# vga_audio.net
KiCad netlist of a schematic drawn in Altium Designer
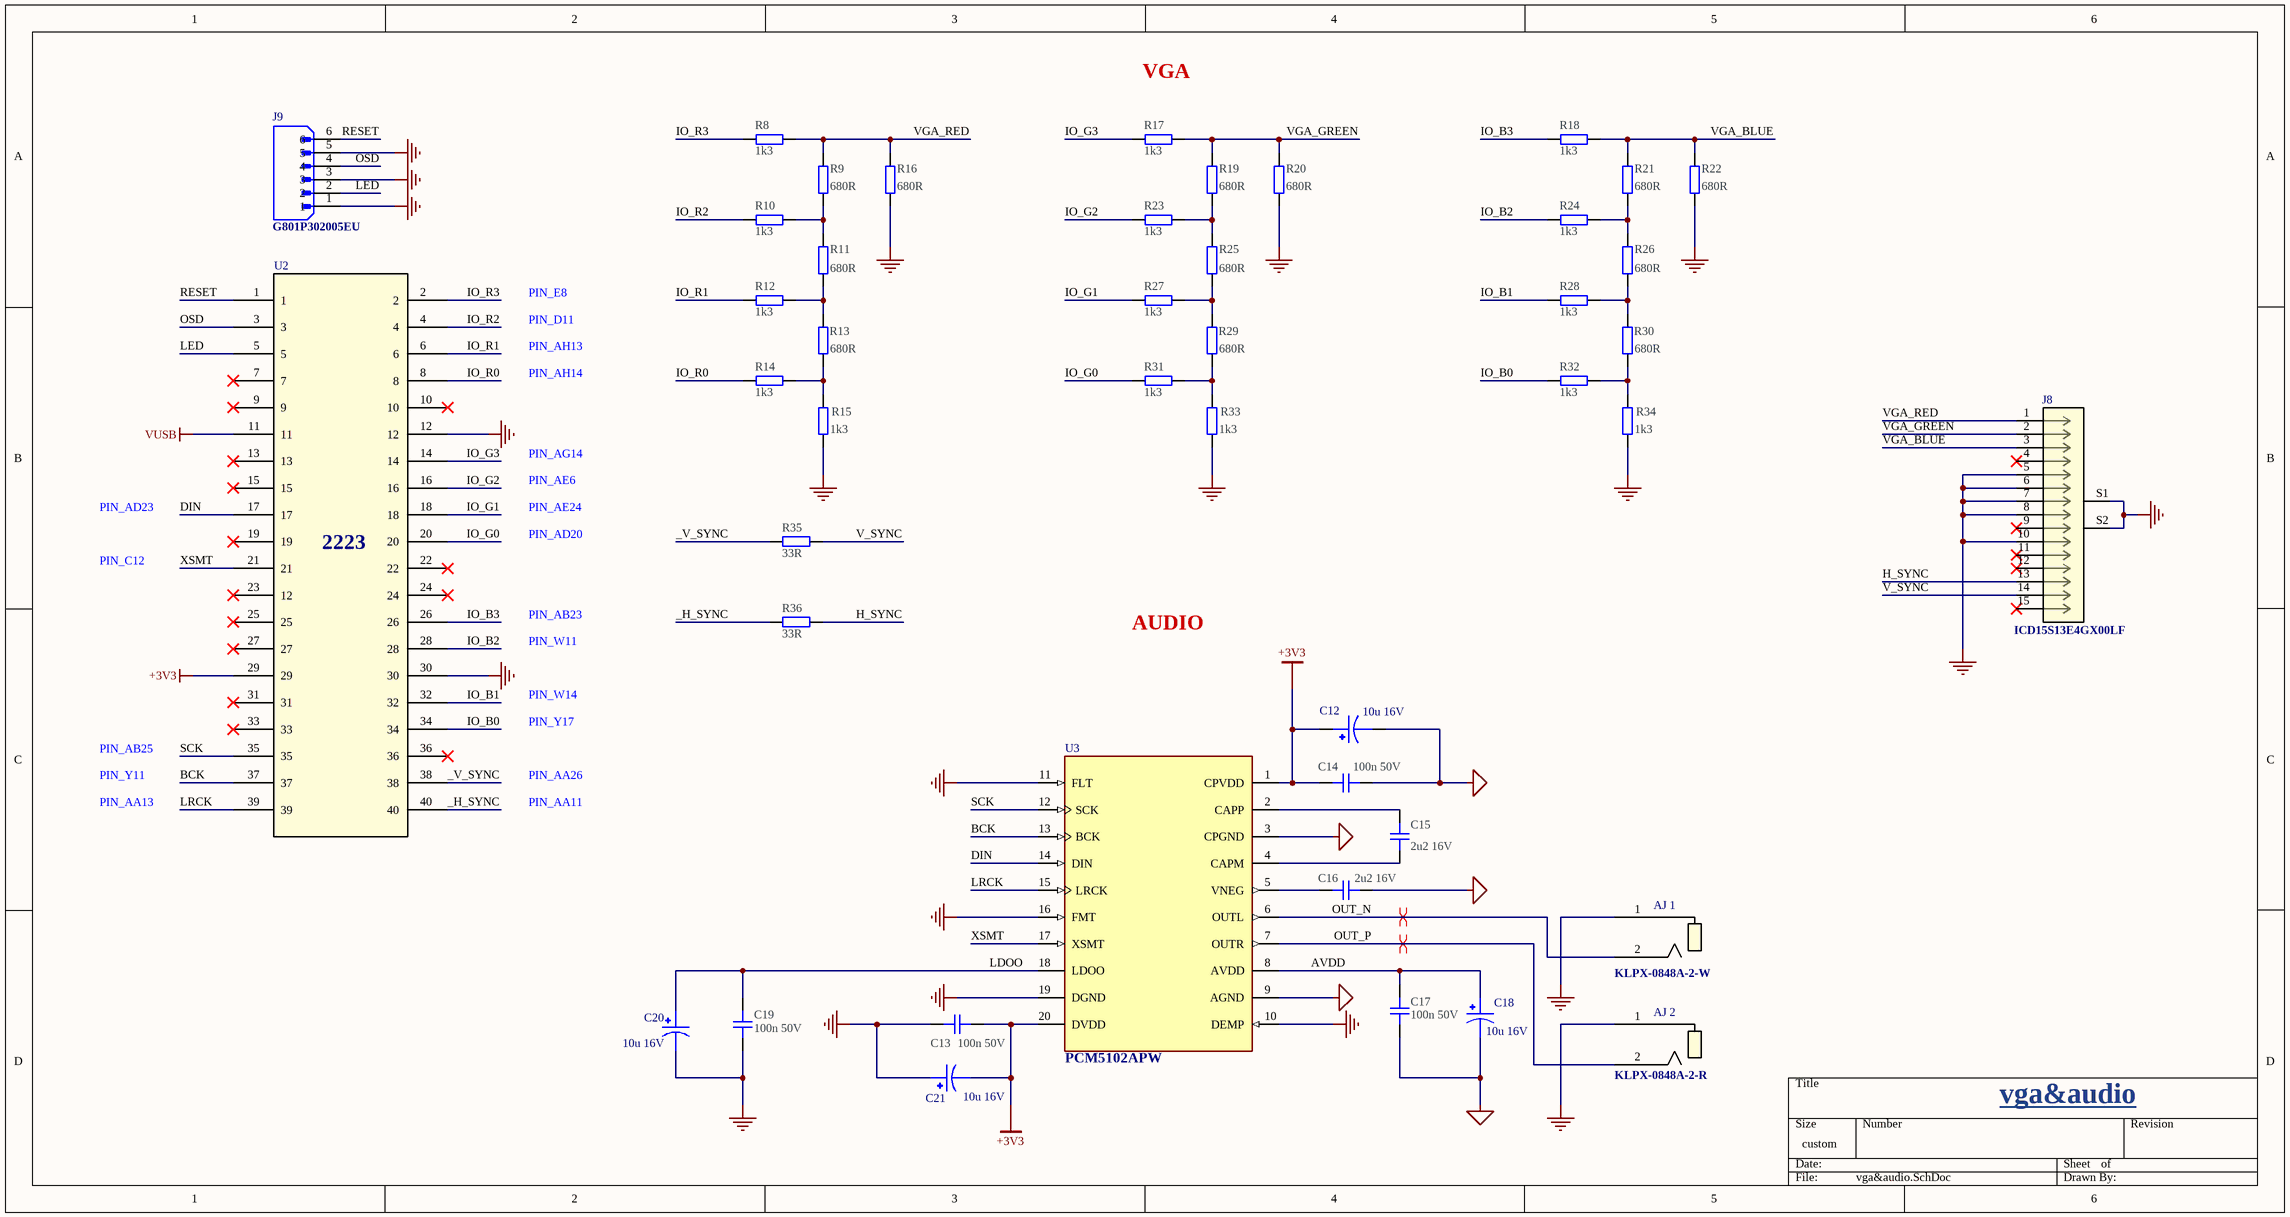
[diagram p0: vga&audio.SchDoc]

(export (version "E")
  (design (tool "Eeschema 10.0.6"))
  (components
    (comp (ref "AJ 1")
      (value "KLPX-0848A-2-W")
      (footprint "KLPX0848A2W")
      (description "Description")
      (fields
        (field (name "MANUFACTURER_PART_NUMBER") "KLPX-0848A-2-R")
        (field (name "COPYRIGHT") "Copyright (C) 2025 Ultra Librarian. All rights reserved.")
      )
      (libsource (lib "Sch_Lib") (part "KLPX-0848A-2-W"))
    )
    (comp (ref "AJ 2")
      (value "KLPX-0848A-2-R")
      (footprint "KLPX0848A2R")
      (description "Description")
      (fields (field (name "COPYRIGHT") "Copyright (C) 2025 Ultra Librarian. All rights reserved."))
      (libsource (lib "Sch_Lib") (part "KLPX-0848A-2-R"))
    )
    (comp (ref "C12")
      (value "10u 16V")
      (footprint "CAPMP3216X180N")
      (description "10 ÂµF Molded Tantalum Capacitors 16 V 1206 (3216 Metric) 3Ohm")
      (fields (field (name "MF") "KYOCERA AVX") (field (name "MP") "TAJA106K016RNJ"))
      (libsource (lib "") (part "TAJA106K016RNJ_1"))
    )
    (comp (ref "C13")
      (value "100n 50V")
      (footprint "CAPC1005X04L")
      (description "Capacitor, X5R, ±20%")
      (fields
        (field (name "PART NUMBER") "C0402-4µ7")
        (field (name "MANUFACTURER") "N.A.")
        (field (name "AUTHOR") "rsk")
      )
      (libsource (lib "Sch_Lib") (part "C0402-4µ7"))
    )
    (comp (ref "C14")
      (value "100n 50V")
      (footprint "CAPC1005X04L")
      (description "Capacitor, X5R, ±20%")
      (fields
        (field (name "PART NUMBER") "C0402-4µ7")
        (field (name "MANUFACTURER") "N.A.")
        (field (name "AUTHOR") "rsk")
      )
      (libsource (lib "Sch_Lib") (part "C0402-4µ7"))
    )
    (comp (ref "C15")
      (value "2u2 16V")
      (footprint "CAPC1005X04L")
      (description "Capacitor, X5R, ±20%")
      (fields
        (field (name "PART NUMBER") "C0402-4µ7")
        (field (name "MANUFACTURER") "N.A.")
        (field (name "AUTHOR") "rsk")
      )
      (libsource (lib "Sch_Lib") (part "C0402-4µ7"))
    )
    (comp (ref "C16")
      (value "2u2 16V")
      (footprint "CAPC1005X04L")
      (description "Capacitor, X5R, ±20%")
      (fields
        (field (name "PART NUMBER") "C0402-4µ7")
        (field (name "MANUFACTURER") "N.A.")
        (field (name "AUTHOR") "rsk")
      )
      (libsource (lib "Sch_Lib") (part "C0402-4µ7"))
    )
    (comp (ref "C17")
      (value "100n 50V")
      (footprint "CAPC1005X04L")
      (description "Capacitor, X5R, ±20%")
      (fields
        (field (name "PART NUMBER") "C0402-4µ7")
        (field (name "MANUFACTURER") "N.A.")
        (field (name "AUTHOR") "rsk")
      )
      (libsource (lib "Sch_Lib") (part "C0402-4µ7"))
    )
    (comp (ref "C18")
      (value "10u 16V")
      (footprint "CAPMP3216X180N")
      (description "10 ÂµF Molded Tantalum Capacitors 16 V 1206 (3216 Metric) 3Ohm")
      (fields (field (name "MF") "KYOCERA AVX") (field (name "MP") "TAJA106K016RNJ"))
      (libsource (lib "") (part "TAJA106K016RNJ_2"))
    )
    (comp (ref "C19")
      (value "100n 50V")
      (footprint "CAPC1005X04L")
      (description "Capacitor, X5R, ±20%")
      (fields
        (field (name "PART NUMBER") "C0402-4µ7")
        (field (name "MANUFACTURER") "N.A.")
        (field (name "AUTHOR") "rsk")
      )
      (libsource (lib "Sch_Lib") (part "C0402-4µ7"))
    )
    (comp (ref "C20")
      (value "10u 16V")
      (footprint "CAPMP3216X180N")
      (description "10 ÂµF Molded Tantalum Capacitors 16 V 1206 (3216 Metric) 3Ohm")
      (fields (field (name "MF") "KYOCERA AVX") (field (name "MP") "TAJA106K016RNJ"))
      (libsource (lib "") (part "TAJA106K016RNJ_2"))
    )
    (comp (ref "C21")
      (value "10u 16V")
      (footprint "CAPMP3216X180N")
      (description "10 ÂµF Molded Tantalum Capacitors 16 V 1206 (3216 Metric) 3Ohm")
      (fields (field (name "MF") "KYOCERA AVX") (field (name "MP") "TAJA106K016RNJ"))
      (libsource (lib "Sch_Lib") (part "TAJA106K016RNJ"))
    )
    (comp (ref "J8")
      (value "ICD15S13E4GX00LF")
      (footprint "AMPHENOL_ICD15S13E4GX00LF")
      (description "Conn High Density D-Sub SKT 15 POS 2.28mm Solder RA Thru-Hole 15 Terminal 1 Port")
      (fields (field (name "MF") "Amphenol"))
      (libsource (lib "Sch_Lib") (part "ICD15S13E4GX00LF"))
    )
    (comp (ref "J9")
      (value "G801P302005EU")
      (footprint "AMPHENOL_G801P302005EU")
      (fields (field (name "MF") "{'manufacturer': u'Amphenol ICC (Commercial Products)'}"))
      (libsource (lib "Sch_Lib") (part "G801P302005EU"))
    )
    (comp (ref "R8")
      (value "1k3")
      (footprint "RESC1005X04L")
      (description "Resistor, ±5%, 0.063W")
      (fields
        (field (name "PART NUMBER") "R0402-0R")
        (field (name "MANUFACTURER") "N.A.")
        (field (name "AUTHOR") "rsk")
      )
      (libsource (lib "Sch_Lib") (part "R0402-0R"))
    )
    (comp (ref "R9")
      (value "680R")
      (footprint "RESC1005X04L")
      (description "Resistor, ±5%, 0.063W")
      (fields
        (field (name "PART NUMBER") "R0402-0R")
        (field (name "MANUFACTURER") "N.A.")
        (field (name "AUTHOR") "rsk")
      )
      (libsource (lib "Sch_Lib") (part "R0402-0R"))
    )
    (comp (ref "R10")
      (value "1k3")
      (footprint "RESC1005X04L")
      (description "Resistor, ±5%, 0.063W")
      (fields
        (field (name "PART NUMBER") "R0402-0R")
        (field (name "MANUFACTURER") "N.A.")
        (field (name "AUTHOR") "rsk")
      )
      (libsource (lib "Sch_Lib") (part "R0402-0R"))
    )
    (comp (ref "R11")
      (value "680R")
      (footprint "RESC1005X04L")
      (description "Resistor, ±5%, 0.063W")
      (fields
        (field (name "PART NUMBER") "R0402-0R")
        (field (name "MANUFACTURER") "N.A.")
        (field (name "AUTHOR") "rsk")
      )
      (libsource (lib "Sch_Lib") (part "R0402-0R"))
    )
    (comp (ref "R12")
      (value "1k3")
      (footprint "RESC1005X04L")
      (description "Resistor, ±5%, 0.063W")
      (fields
        (field (name "PART NUMBER") "R0402-0R")
        (field (name "MANUFACTURER") "N.A.")
        (field (name "AUTHOR") "rsk")
      )
      (libsource (lib "Sch_Lib") (part "R0402-0R"))
    )
    (comp (ref "R13")
      (value "680R")
      (footprint "RESC1005X04L")
      (description "Resistor, ±5%, 0.063W")
      (fields
        (field (name "PART NUMBER") "R0402-0R")
        (field (name "MANUFACTURER") "N.A.")
        (field (name "AUTHOR") "rsk")
      )
      (libsource (lib "Sch_Lib") (part "R0402-0R"))
    )
    (comp (ref "R14")
      (value "1k3")
      (footprint "RESC1005X04L")
      (description "Resistor, ±5%, 0.063W")
      (fields
        (field (name "PART NUMBER") "R0402-0R")
        (field (name "MANUFACTURER") "N.A.")
        (field (name "AUTHOR") "rsk")
      )
      (libsource (lib "Sch_Lib") (part "R0402-0R"))
    )
    (comp (ref "R15")
      (value "1k3")
      (footprint "RESC1005X04L")
      (description "Resistor, ±5%, 0.063W")
      (fields
        (field (name "PART NUMBER") "R0402-0R")
        (field (name "MANUFACTURER") "N.A.")
        (field (name "AUTHOR") "rsk")
      )
      (libsource (lib "Sch_Lib") (part "R0402-0R"))
    )
    (comp (ref "R16")
      (value "680R")
      (footprint "RESC1005X04L")
      (description "Resistor, ±5%, 0.063W")
      (fields
        (field (name "PART NUMBER") "R0402-0R")
        (field (name "MANUFACTURER") "N.A.")
        (field (name "AUTHOR") "rsk")
      )
      (libsource (lib "Sch_Lib") (part "R0402-0R"))
    )
    (comp (ref "R17")
      (value "1k3")
      (footprint "RESC1005X04L")
      (description "Resistor, ±5%, 0.063W")
      (fields
        (field (name "PART NUMBER") "R0402-0R")
        (field (name "MANUFACTURER") "N.A.")
        (field (name "AUTHOR") "rsk")
      )
      (libsource (lib "Sch_Lib") (part "R0402-0R"))
    )
    (comp (ref "R18")
      (value "1k3")
      (footprint "RESC1005X04L")
      (description "Resistor, ±5%, 0.063W")
      (fields
        (field (name "PART NUMBER") "R0402-0R")
        (field (name "MANUFACTURER") "N.A.")
        (field (name "AUTHOR") "rsk")
      )
      (libsource (lib "Sch_Lib") (part "R0402-0R"))
    )
    (comp (ref "R19")
      (value "680R")
      (footprint "RESC1005X04L")
      (description "Resistor, ±5%, 0.063W")
      (fields
        (field (name "PART NUMBER") "R0402-0R")
        (field (name "MANUFACTURER") "N.A.")
        (field (name "AUTHOR") "rsk")
      )
      (libsource (lib "Sch_Lib") (part "R0402-0R"))
    )
    (comp (ref "R20")
      (value "680R")
      (footprint "RESC1005X04L")
      (description "Resistor, ±5%, 0.063W")
      (fields
        (field (name "PART NUMBER") "R0402-0R")
        (field (name "MANUFACTURER") "N.A.")
        (field (name "AUTHOR") "rsk")
      )
      (libsource (lib "Sch_Lib") (part "R0402-0R"))
    )
    (comp (ref "R21")
      (value "680R")
      (footprint "RESC1005X04L")
      (description "Resistor, ±5%, 0.063W")
      (fields
        (field (name "PART NUMBER") "R0402-0R")
        (field (name "MANUFACTURER") "N.A.")
        (field (name "AUTHOR") "rsk")
      )
      (libsource (lib "Sch_Lib") (part "R0402-0R"))
    )
    (comp (ref "R22")
      (value "680R")
      (footprint "RESC1005X04L")
      (description "Resistor, ±5%, 0.063W")
      (fields
        (field (name "PART NUMBER") "R0402-0R")
        (field (name "MANUFACTURER") "N.A.")
        (field (name "AUTHOR") "rsk")
      )
      (libsource (lib "Sch_Lib") (part "R0402-0R"))
    )
    (comp (ref "R23")
      (value "1k3")
      (footprint "RESC1005X04L")
      (description "Resistor, ±5%, 0.063W")
      (fields
        (field (name "PART NUMBER") "R0402-0R")
        (field (name "MANUFACTURER") "N.A.")
        (field (name "AUTHOR") "rsk")
      )
      (libsource (lib "Sch_Lib") (part "R0402-0R"))
    )
    (comp (ref "R24")
      (value "1k3")
      (footprint "RESC1005X04L")
      (description "Resistor, ±5%, 0.063W")
      (fields
        (field (name "PART NUMBER") "R0402-0R")
        (field (name "MANUFACTURER") "N.A.")
        (field (name "AUTHOR") "rsk")
      )
      (libsource (lib "Sch_Lib") (part "R0402-0R"))
    )
    (comp (ref "R25")
      (value "680R")
      (footprint "RESC1005X04L")
      (description "Resistor, ±5%, 0.063W")
      (fields
        (field (name "PART NUMBER") "R0402-0R")
        (field (name "MANUFACTURER") "N.A.")
        (field (name "AUTHOR") "rsk")
      )
      (libsource (lib "Sch_Lib") (part "R0402-0R"))
    )
    (comp (ref "R26")
      (value "680R")
      (footprint "RESC1005X04L")
      (description "Resistor, ±5%, 0.063W")
      (fields
        (field (name "PART NUMBER") "R0402-0R")
        (field (name "MANUFACTURER") "N.A.")
        (field (name "AUTHOR") "rsk")
      )
      (libsource (lib "Sch_Lib") (part "R0402-0R"))
    )
    (comp (ref "R27")
      (value "1k3")
      (footprint "RESC1005X04L")
      (description "Resistor, ±5%, 0.063W")
      (fields
        (field (name "PART NUMBER") "R0402-0R")
        (field (name "MANUFACTURER") "N.A.")
        (field (name "AUTHOR") "rsk")
      )
      (libsource (lib "Sch_Lib") (part "R0402-0R"))
    )
    (comp (ref "R28")
      (value "1k3")
      (footprint "RESC1005X04L")
      (description "Resistor, ±5%, 0.063W")
      (fields
        (field (name "PART NUMBER") "R0402-0R")
        (field (name "MANUFACTURER") "N.A.")
        (field (name "AUTHOR") "rsk")
      )
      (libsource (lib "Sch_Lib") (part "R0402-0R"))
    )
    (comp (ref "R29")
      (value "680R")
      (footprint "RESC1005X04L")
      (description "Resistor, ±5%, 0.063W")
      (fields
        (field (name "PART NUMBER") "R0402-0R")
        (field (name "MANUFACTURER") "N.A.")
        (field (name "AUTHOR") "rsk")
      )
      (libsource (lib "Sch_Lib") (part "R0402-0R"))
    )
    (comp (ref "R30")
      (value "680R")
      (footprint "RESC1005X04L")
      (description "Resistor, ±5%, 0.063W")
      (fields
        (field (name "PART NUMBER") "R0402-0R")
        (field (name "MANUFACTURER") "N.A.")
        (field (name "AUTHOR") "rsk")
      )
      (libsource (lib "Sch_Lib") (part "R0402-0R"))
    )
    (comp (ref "R31")
      (value "1k3")
      (footprint "RESC1005X04L")
      (description "Resistor, ±5%, 0.063W")
      (fields
        (field (name "PART NUMBER") "R0402-0R")
        (field (name "MANUFACTURER") "N.A.")
        (field (name "AUTHOR") "rsk")
      )
      (libsource (lib "Sch_Lib") (part "R0402-0R"))
    )
    (comp (ref "R32")
      (value "1k3")
      (footprint "RESC1005X04L")
      (description "Resistor, ±5%, 0.063W")
      (fields
        (field (name "PART NUMBER") "R0402-0R")
        (field (name "MANUFACTURER") "N.A.")
        (field (name "AUTHOR") "rsk")
      )
      (libsource (lib "Sch_Lib") (part "R0402-0R"))
    )
    (comp (ref "R33")
      (value "1k3")
      (footprint "RESC1005X04L")
      (description "Resistor, ±5%, 0.063W")
      (fields
        (field (name "PART NUMBER") "R0402-0R")
        (field (name "MANUFACTURER") "N.A.")
        (field (name "AUTHOR") "rsk")
      )
      (libsource (lib "Sch_Lib") (part "R0402-0R"))
    )
    (comp (ref "R34")
      (value "1k3")
      (footprint "RESC1005X04L")
      (description "Resistor, ±5%, 0.063W")
      (fields
        (field (name "PART NUMBER") "R0402-0R")
        (field (name "MANUFACTURER") "N.A.")
        (field (name "AUTHOR") "rsk")
      )
      (libsource (lib "Sch_Lib") (part "R0402-0R"))
    )
    (comp (ref "R35")
      (value "33R")
      (footprint "RESC1005X04L")
      (description "Resistor, ±5%, 0.063W")
      (fields
        (field (name "PART NUMBER") "R0402-0R")
        (field (name "MANUFACTURER") "N.A.")
        (field (name "AUTHOR") "rsk")
      )
      (libsource (lib "Sch_Lib") (part "R0402-0R"))
    )
    (comp (ref "R36")
      (value "33R")
      (footprint "RESC1005X04L")
      (description "Resistor, ±5%, 0.063W")
      (fields
        (field (name "PART NUMBER") "R0402-0R")
        (field (name "MANUFACTURER") "N.A.")
        (field (name "AUTHOR") "rsk")
      )
      (libsource (lib "Sch_Lib") (part "R0402-0R"))
    )
    (comp (ref "U2")
      (value "2223")
      (footprint "2223_ADA")
      (description "Description")
      (fields (field (name "COPYRIGHT") "Copyright (C) 2025 Ultra Librarian. All rights reserved."))
      (libsource (lib "Sch_Lib") (part "2223"))
    )
    (comp (ref "U3")
      (value "PCM5102APW")
      (footprint "Fp_Lib:SOP65P640X120-20N")
      (fields (field (name "MF") "Texas Instruments"))
      (libsource (lib "Sch_Lib") (part "PCM5102APW"))
    )
  )
  (nets
    (net (code "1") (name "+3V3") (class "Default")
      (node (ref "C12") (pin "1") (pinfunction "1_1") (pintype "passive"))
      (node (ref "C13") (pin "1") (pinfunction "1_1") (pintype "passive"))
      (node (ref "C14") (pin "2") (pinfunction "2_2") (pintype "passive"))
      (node (ref "C21") (pin "2") (pinfunction "2_2") (pintype "passive"))
      (node (ref "U2") (pin "29") (pinfunction "29_29") (pintype "passive"))
      (node (ref "U3") (pin "1") (pinfunction "CPVDD_1") (pintype "power_in"))
      (node (ref "U3") (pin "20") (pinfunction "DVDD_20") (pintype "power_in"))
    )
    (net (code "2") (name "/AVDD") (class "Default")
      (node (ref "C17") (pin "1") (pinfunction "1_1") (pintype "passive"))
      (node (ref "C18") (pin "1") (pinfunction "1_1") (pintype "passive"))
      (node (ref "U3") (pin "8") (pinfunction "AVDD_8") (pintype "power_in"))
    )
    (net (code "3") (name "/BCK") (class "Default")
      (node (ref "U2") (pin "37") (pinfunction "37_37") (pintype "passive"))
      (node (ref "U3") (pin "13") (pinfunction "BCK_13") (pintype "input"))
    )
    (net (code "4") (name "/DIN") (class "Default")
      (node (ref "U2") (pin "17") (pinfunction "17_17") (pintype "passive"))
      (node (ref "U3") (pin "14") (pinfunction "DIN_14") (pintype "input"))
    )
    (net (code "5") (name "/H_SYNC") (class "Default")
      (node (ref "J8") (pin "13") (pinfunction "13_13") (pintype "passive"))
      (node (ref "R36") (pin "2") (pinfunction "2_2") (pintype "passive"))
    )
    (net (code "6") (name "/IO_B0") (class "Default")
      (node (ref "R32") (pin "1") (pinfunction "1_1") (pintype "passive"))
      (node (ref "U2") (pin "34") (pinfunction "34_34") (pintype "passive"))
    )
    (net (code "7") (name "/IO_B1") (class "Default")
      (node (ref "R28") (pin "1") (pinfunction "1_1") (pintype "passive"))
      (node (ref "U2") (pin "32") (pinfunction "32_32") (pintype "passive"))
    )
    (net (code "8") (name "/IO_B2") (class "Default")
      (node (ref "R24") (pin "1") (pinfunction "1_1") (pintype "passive"))
      (node (ref "U2") (pin "28") (pinfunction "28_28") (pintype "passive"))
    )
    (net (code "9") (name "/IO_B3") (class "Default")
      (node (ref "R18") (pin "1") (pinfunction "1_1") (pintype "passive"))
      (node (ref "U2") (pin "26") (pinfunction "26_26") (pintype "passive"))
    )
    (net (code "10") (name "/IO_G0") (class "Default")
      (node (ref "R31") (pin "1") (pinfunction "1_1") (pintype "passive"))
      (node (ref "U2") (pin "20") (pinfunction "20_20") (pintype "passive"))
    )
    (net (code "11") (name "/IO_G1") (class "Default")
      (node (ref "R27") (pin "1") (pinfunction "1_1") (pintype "passive"))
      (node (ref "U2") (pin "18") (pinfunction "18_18") (pintype "passive"))
    )
    (net (code "12") (name "/IO_G2") (class "Default")
      (node (ref "R23") (pin "1") (pinfunction "1_1") (pintype "passive"))
      (node (ref "U2") (pin "16") (pinfunction "16_16") (pintype "passive"))
    )
    (net (code "13") (name "/IO_G3") (class "Default")
      (node (ref "R17") (pin "1") (pinfunction "1_1") (pintype "passive"))
      (node (ref "U2") (pin "14") (pinfunction "14_14") (pintype "passive"))
    )
    (net (code "14") (name "/IO_R0") (class "Default")
      (node (ref "R14") (pin "1") (pinfunction "1_1") (pintype "passive"))
      (node (ref "U2") (pin "8") (pinfunction "8_8") (pintype "passive"))
    )
    (net (code "15") (name "/IO_R1") (class "Default")
      (node (ref "R12") (pin "1") (pinfunction "1_1") (pintype "passive"))
      (node (ref "U2") (pin "6") (pinfunction "6_6") (pintype "passive"))
    )
    (net (code "16") (name "/IO_R2") (class "Default")
      (node (ref "R10") (pin "1") (pinfunction "1_1") (pintype "passive"))
      (node (ref "U2") (pin "4") (pinfunction "4_4") (pintype "passive"))
    )
    (net (code "17") (name "/IO_R3") (class "Default")
      (node (ref "R8") (pin "1") (pinfunction "1_1") (pintype "passive"))
      (node (ref "U2") (pin "2") (pinfunction "2_2") (pintype "passive"))
    )
    (net (code "18") (name "/LDOO") (class "Default")
      (node (ref "C19") (pin "1") (pinfunction "1_1") (pintype "passive"))
      (node (ref "C20") (pin "1") (pinfunction "1_1") (pintype "passive"))
      (node (ref "U3") (pin "18") (pinfunction "LDOO_18") (pintype "power_in"))
    )
    (net (code "19") (name "/LED") (class "Default")
      (node (ref "J9") (pin "2") (pinfunction "2_2") (pintype "passive"))
      (node (ref "U2") (pin "5") (pinfunction "5_5") (pintype "passive"))
    )
    (net (code "20") (name "/LRCK") (class "Default")
      (node (ref "U2") (pin "39") (pinfunction "39_39") (pintype "passive"))
      (node (ref "U3") (pin "15") (pinfunction "LRCK_15") (pintype "input"))
    )
    (net (code "21") (name "/OSD") (class "Default")
      (node (ref "J9") (pin "4") (pinfunction "4_4") (pintype "passive"))
      (node (ref "U2") (pin "3") (pinfunction "3_3") (pintype "passive"))
    )
    (net (code "22") (name "/OUT_N") (class "Default")
      (node (ref "AJ 1") (pin "2") (pinfunction "2_2") (pintype "passive"))
      (node (ref "U3") (pin "6") (pinfunction "OUTL_6") (pintype "output"))
    )
    (net (code "23") (name "/OUT_P") (class "Default")
      (node (ref "AJ 2") (pin "2") (pinfunction "2_2") (pintype "passive"))
      (node (ref "U3") (pin "7") (pinfunction "OUTR_7") (pintype "output"))
    )
    (net (code "24") (name "/RESET") (class "Default")
      (node (ref "J9") (pin "6") (pinfunction "6_6") (pintype "passive"))
      (node (ref "U2") (pin "1") (pinfunction "1_1") (pintype "passive"))
    )
    (net (code "25") (name "/SCK") (class "Default")
      (node (ref "U2") (pin "35") (pinfunction "35_35") (pintype "passive"))
      (node (ref "U3") (pin "12") (pinfunction "SCK_12") (pintype "input"))
    )
    (net (code "26") (name "/VGA_BLUE") (class "Default")
      (node (ref "J8") (pin "3") (pinfunction "3_3") (pintype "passive"))
      (node (ref "R18") (pin "2") (pinfunction "2_2") (pintype "passive"))
      (node (ref "R21") (pin "2") (pinfunction "2_2") (pintype "passive"))
      (node (ref "R22") (pin "2") (pinfunction "2_2") (pintype "passive"))
    )
    (net (code "27") (name "/VGA_GREEN") (class "Default")
      (node (ref "J8") (pin "2") (pinfunction "2_2") (pintype "passive"))
      (node (ref "R17") (pin "2") (pinfunction "2_2") (pintype "passive"))
      (node (ref "R19") (pin "2") (pinfunction "2_2") (pintype "passive"))
      (node (ref "R20") (pin "2") (pinfunction "2_2") (pintype "passive"))
    )
    (net (code "28") (name "/VGA_RED") (class "Default")
      (node (ref "J8") (pin "1") (pinfunction "1_1") (pintype "passive"))
      (node (ref "R16") (pin "2") (pinfunction "2_2") (pintype "passive"))
      (node (ref "R8") (pin "2") (pinfunction "2_2") (pintype "passive"))
      (node (ref "R9") (pin "2") (pinfunction "2_2") (pintype "passive"))
    )
    (net (code "29") (name "/V_SYNC") (class "Default")
      (node (ref "J8") (pin "14") (pinfunction "14_14") (pintype "passive"))
      (node (ref "R35") (pin "2") (pinfunction "2_2") (pintype "passive"))
    )
    (net (code "30") (name "/XSMT") (class "Default")
      (node (ref "U2") (pin "21") (pinfunction "21_21") (pintype "passive"))
      (node (ref "U3") (pin "17") (pinfunction "XSMT_17") (pintype "input"))
    )
    (net (code "31") (name "/_H_SYNC") (class "Default")
      (node (ref "R36") (pin "1") (pinfunction "1_1") (pintype "passive"))
      (node (ref "U2") (pin "40") (pinfunction "40_40") (pintype "passive"))
    )
    (net (code "32") (name "/_V_SYNC") (class "Default")
      (node (ref "R35") (pin "1") (pinfunction "1_1") (pintype "passive"))
      (node (ref "U2") (pin "38") (pinfunction "38_38") (pintype "passive"))
    )
    (net (code "33") (name "AGND") (class "Default")
      (node (ref "C12") (pin "2") (pinfunction "2_2") (pintype "passive"))
      (node (ref "C14") (pin "1") (pinfunction "1_1") (pintype "passive"))
      (node (ref "C16") (pin "2") (pinfunction "2_2") (pintype "passive"))
      (node (ref "C17") (pin "2") (pinfunction "2_2") (pintype "passive"))
      (node (ref "C18") (pin "2") (pinfunction "2_2") (pintype "passive"))
      (node (ref "U3") (pin "3") (pinfunction "CPGND_3") (pintype "power_in"))
      (node (ref "U3") (pin "9") (pinfunction "AGND_9") (pintype "power_in"))
    )
    (net (code "34") (name "GND") (class "Default")
      (node (ref "AJ 1") (pin "1") (pinfunction "1_1") (pintype "passive"))
      (node (ref "AJ 2") (pin "1") (pinfunction "1_1") (pintype "passive"))
      (node (ref "C13") (pin "2") (pinfunction "2_2") (pintype "passive"))
      (node (ref "C19") (pin "2") (pinfunction "2_2") (pintype "passive"))
      (node (ref "C20") (pin "2") (pinfunction "2_2") (pintype "passive"))
      (node (ref "C21") (pin "1") (pinfunction "1_1") (pintype "passive"))
      (node (ref "J8") (pin "10") (pinfunction "10_10") (pintype "passive"))
      (node (ref "J8") (pin "5") (pinfunction "5_5") (pintype "passive"))
      (node (ref "J8") (pin "6") (pinfunction "6_6") (pintype "passive"))
      (node (ref "J8") (pin "7") (pinfunction "7_7") (pintype "passive"))
      (node (ref "J8") (pin "8") (pinfunction "8_8") (pintype "passive"))
      (node (ref "J8") (pin "S1") (pinfunction "SHIELD_S1") (pintype "passive"))
      (node (ref "J8") (pin "S2") (pinfunction "SHIELD_S2") (pintype "passive"))
      (node (ref "J9") (pin "1") (pinfunction "1_1") (pintype "passive"))
      (node (ref "J9") (pin "3") (pinfunction "3_3") (pintype "passive"))
      (node (ref "J9") (pin "5") (pinfunction "5_5") (pintype "passive"))
      (node (ref "R15") (pin "2") (pinfunction "2_2") (pintype "passive"))
      (node (ref "R16") (pin "1") (pinfunction "1_1") (pintype "passive"))
      (node (ref "R20") (pin "1") (pinfunction "1_1") (pintype "passive"))
      (node (ref "R22") (pin "1") (pinfunction "1_1") (pintype "passive"))
      (node (ref "R33") (pin "2") (pinfunction "2_2") (pintype "passive"))
      (node (ref "R34") (pin "2") (pinfunction "2_2") (pintype "passive"))
      (node (ref "U2") (pin "12") (pinfunction "12_12") (pintype "passive"))
      (node (ref "U2") (pin "30") (pinfunction "30_30") (pintype "passive"))
      (node (ref "U3") (pin "10") (pinfunction "DEMP_10") (pintype "input"))
      (node (ref "U3") (pin "11") (pinfunction "FLT_11") (pintype "input"))
      (node (ref "U3") (pin "16") (pinfunction "FMT_16") (pintype "input"))
      (node (ref "U3") (pin "19") (pinfunction "DGND_19") (pintype "power_in"))
    )
    (net (code "35") (name "Net-(R10-Pad2)") (class "Default")
      (node (ref "R10") (pin "2") (pinfunction "2_2") (pintype "passive"))
      (node (ref "R11") (pin "2") (pinfunction "2_2") (pintype "passive"))
      (node (ref "R9") (pin "1") (pinfunction "1_1") (pintype "passive"))
    )
    (net (code "36") (name "Net-(R11-Pad1)") (class "Default")
      (node (ref "R11") (pin "1") (pinfunction "1_1") (pintype "passive"))
      (node (ref "R12") (pin "2") (pinfunction "2_2") (pintype "passive"))
      (node (ref "R13") (pin "2") (pinfunction "2_2") (pintype "passive"))
    )
    (net (code "37") (name "Net-(R13-Pad1)") (class "Default")
      (node (ref "R13") (pin "1") (pinfunction "1_1") (pintype "passive"))
      (node (ref "R14") (pin "2") (pinfunction "2_2") (pintype "passive"))
      (node (ref "R15") (pin "1") (pinfunction "1_1") (pintype "passive"))
    )
    (net (code "38") (name "Net-(R19-Pad1)") (class "Default")
      (node (ref "R19") (pin "1") (pinfunction "1_1") (pintype "passive"))
      (node (ref "R23") (pin "2") (pinfunction "2_2") (pintype "passive"))
      (node (ref "R25") (pin "2") (pinfunction "2_2") (pintype "passive"))
    )
    (net (code "39") (name "Net-(R21-Pad1)") (class "Default")
      (node (ref "R21") (pin "1") (pinfunction "1_1") (pintype "passive"))
      (node (ref "R24") (pin "2") (pinfunction "2_2") (pintype "passive"))
      (node (ref "R26") (pin "2") (pinfunction "2_2") (pintype "passive"))
    )
    (net (code "40") (name "Net-(R25-Pad1)") (class "Default")
      (node (ref "R25") (pin "1") (pinfunction "1_1") (pintype "passive"))
      (node (ref "R27") (pin "2") (pinfunction "2_2") (pintype "passive"))
      (node (ref "R29") (pin "2") (pinfunction "2_2") (pintype "passive"))
    )
    (net (code "41") (name "Net-(R26-Pad1)") (class "Default")
      (node (ref "R26") (pin "1") (pinfunction "1_1") (pintype "passive"))
      (node (ref "R28") (pin "2") (pinfunction "2_2") (pintype "passive"))
      (node (ref "R30") (pin "2") (pinfunction "2_2") (pintype "passive"))
    )
    (net (code "42") (name "Net-(R29-Pad1)") (class "Default")
      (node (ref "R29") (pin "1") (pinfunction "1_1") (pintype "passive"))
      (node (ref "R31") (pin "2") (pinfunction "2_2") (pintype "passive"))
      (node (ref "R33") (pin "1") (pinfunction "1_1") (pintype "passive"))
    )
    (net (code "43") (name "Net-(R30-Pad1)") (class "Default")
      (node (ref "R30") (pin "1") (pinfunction "1_1") (pintype "passive"))
      (node (ref "R32") (pin "2") (pinfunction "2_2") (pintype "passive"))
      (node (ref "R34") (pin "1") (pinfunction "1_1") (pintype "passive"))
    )
    (net (code "44") (name "Net-(U3-CAPM)") (class "Default")
      (node (ref "C15") (pin "2") (pinfunction "2_2") (pintype "passive"))
      (node (ref "U3") (pin "4") (pinfunction "CAPM_4") (pintype "passive"))
    )
    (net (code "45") (name "Net-(U3-CAPP)") (class "Default")
      (node (ref "C15") (pin "1") (pinfunction "1_1") (pintype "passive"))
      (node (ref "U3") (pin "2") (pinfunction "CAPP_2") (pintype "passive"))
    )
    (net (code "46") (name "Net-(U3-VNEG)") (class "Default")
      (node (ref "C16") (pin "1") (pinfunction "1_1") (pintype "passive"))
      (node (ref "U3") (pin "5") (pinfunction "VNEG_5") (pintype "output"))
    )
    (net (code "47") (name "VUSB") (class "Default")
      (node (ref "U2") (pin "11") (pinfunction "11_11") (pintype "passive"))
    )
    (net (code "48") (name "unconnected-(J8-Pad4)") (class "Default")
      (node (ref "J8") (pin "4") (pinfunction "4_4") (pintype "passive+no_connect"))
    )
    (net (code "49") (name "unconnected-(J8-Pad9)") (class "Default")
      (node (ref "J8") (pin "9") (pinfunction "9_9") (pintype "passive+no_connect"))
    )
    (net (code "50") (name "unconnected-(J8-Pad11)") (class "Default")
      (node (ref "J8") (pin "11") (pinfunction "11_11") (pintype "passive+no_connect"))
    )
    (net (code "51") (name "unconnected-(J8-Pad12)") (class "Default")
      (node (ref "J8") (pin "12") (pinfunction "12_12") (pintype "passive+no_connect"))
    )
    (net (code "52") (name "unconnected-(J8-Pad15)") (class "Default")
      (node (ref "J8") (pin "15") (pinfunction "15_15") (pintype "passive+no_connect"))
    )
    (net (code "53") (name "unconnected-(U2-12-Pad23)") (class "Default")
      (node (ref "U2") (pin "23") (pinfunction "12_23") (pintype "passive+no_connect"))
    )
    (net (code "54") (name "unconnected-(U2-Pad7)") (class "Default")
      (node (ref "U2") (pin "7") (pinfunction "7_7") (pintype "passive+no_connect"))
    )
    (net (code "55") (name "unconnected-(U2-Pad9)") (class "Default")
      (node (ref "U2") (pin "9") (pinfunction "9_9") (pintype "passive+no_connect"))
    )
    (net (code "56") (name "unconnected-(U2-Pad10)") (class "Default")
      (node (ref "U2") (pin "10") (pinfunction "10_10") (pintype "passive+no_connect"))
    )
    (net (code "57") (name "unconnected-(U2-Pad13)") (class "Default")
      (node (ref "U2") (pin "13") (pinfunction "13_13") (pintype "passive+no_connect"))
    )
    (net (code "58") (name "unconnected-(U2-Pad15)") (class "Default")
      (node (ref "U2") (pin "15") (pinfunction "15_15") (pintype "passive+no_connect"))
    )
    (net (code "59") (name "unconnected-(U2-Pad19)") (class "Default")
      (node (ref "U2") (pin "19") (pinfunction "19_19") (pintype "passive+no_connect"))
    )
    (net (code "60") (name "unconnected-(U2-Pad22)") (class "Default")
      (node (ref "U2") (pin "22") (pinfunction "22_22") (pintype "passive+no_connect"))
    )
    (net (code "61") (name "unconnected-(U2-Pad24)") (class "Default")
      (node (ref "U2") (pin "24") (pinfunction "24_24") (pintype "passive+no_connect"))
    )
    (net (code "62") (name "unconnected-(U2-Pad25)") (class "Default")
      (node (ref "U2") (pin "25") (pinfunction "25_25") (pintype "passive+no_connect"))
    )
    (net (code "63") (name "unconnected-(U2-Pad27)") (class "Default")
      (node (ref "U2") (pin "27") (pinfunction "27_27") (pintype "passive+no_connect"))
    )
    (net (code "64") (name "unconnected-(U2-Pad31)") (class "Default")
      (node (ref "U2") (pin "31") (pinfunction "31_31") (pintype "passive+no_connect"))
    )
    (net (code "65") (name "unconnected-(U2-Pad33)") (class "Default")
      (node (ref "U2") (pin "33") (pinfunction "33_33") (pintype "passive+no_connect"))
    )
    (net (code "66") (name "unconnected-(U2-Pad36)") (class "Default")
      (node (ref "U2") (pin "36") (pinfunction "36_36") (pintype "passive+no_connect"))
    )
  )
)
